# SingleSupplyAudioAmp.net
KiCad netlist of a schematic drawn in Altium Designer
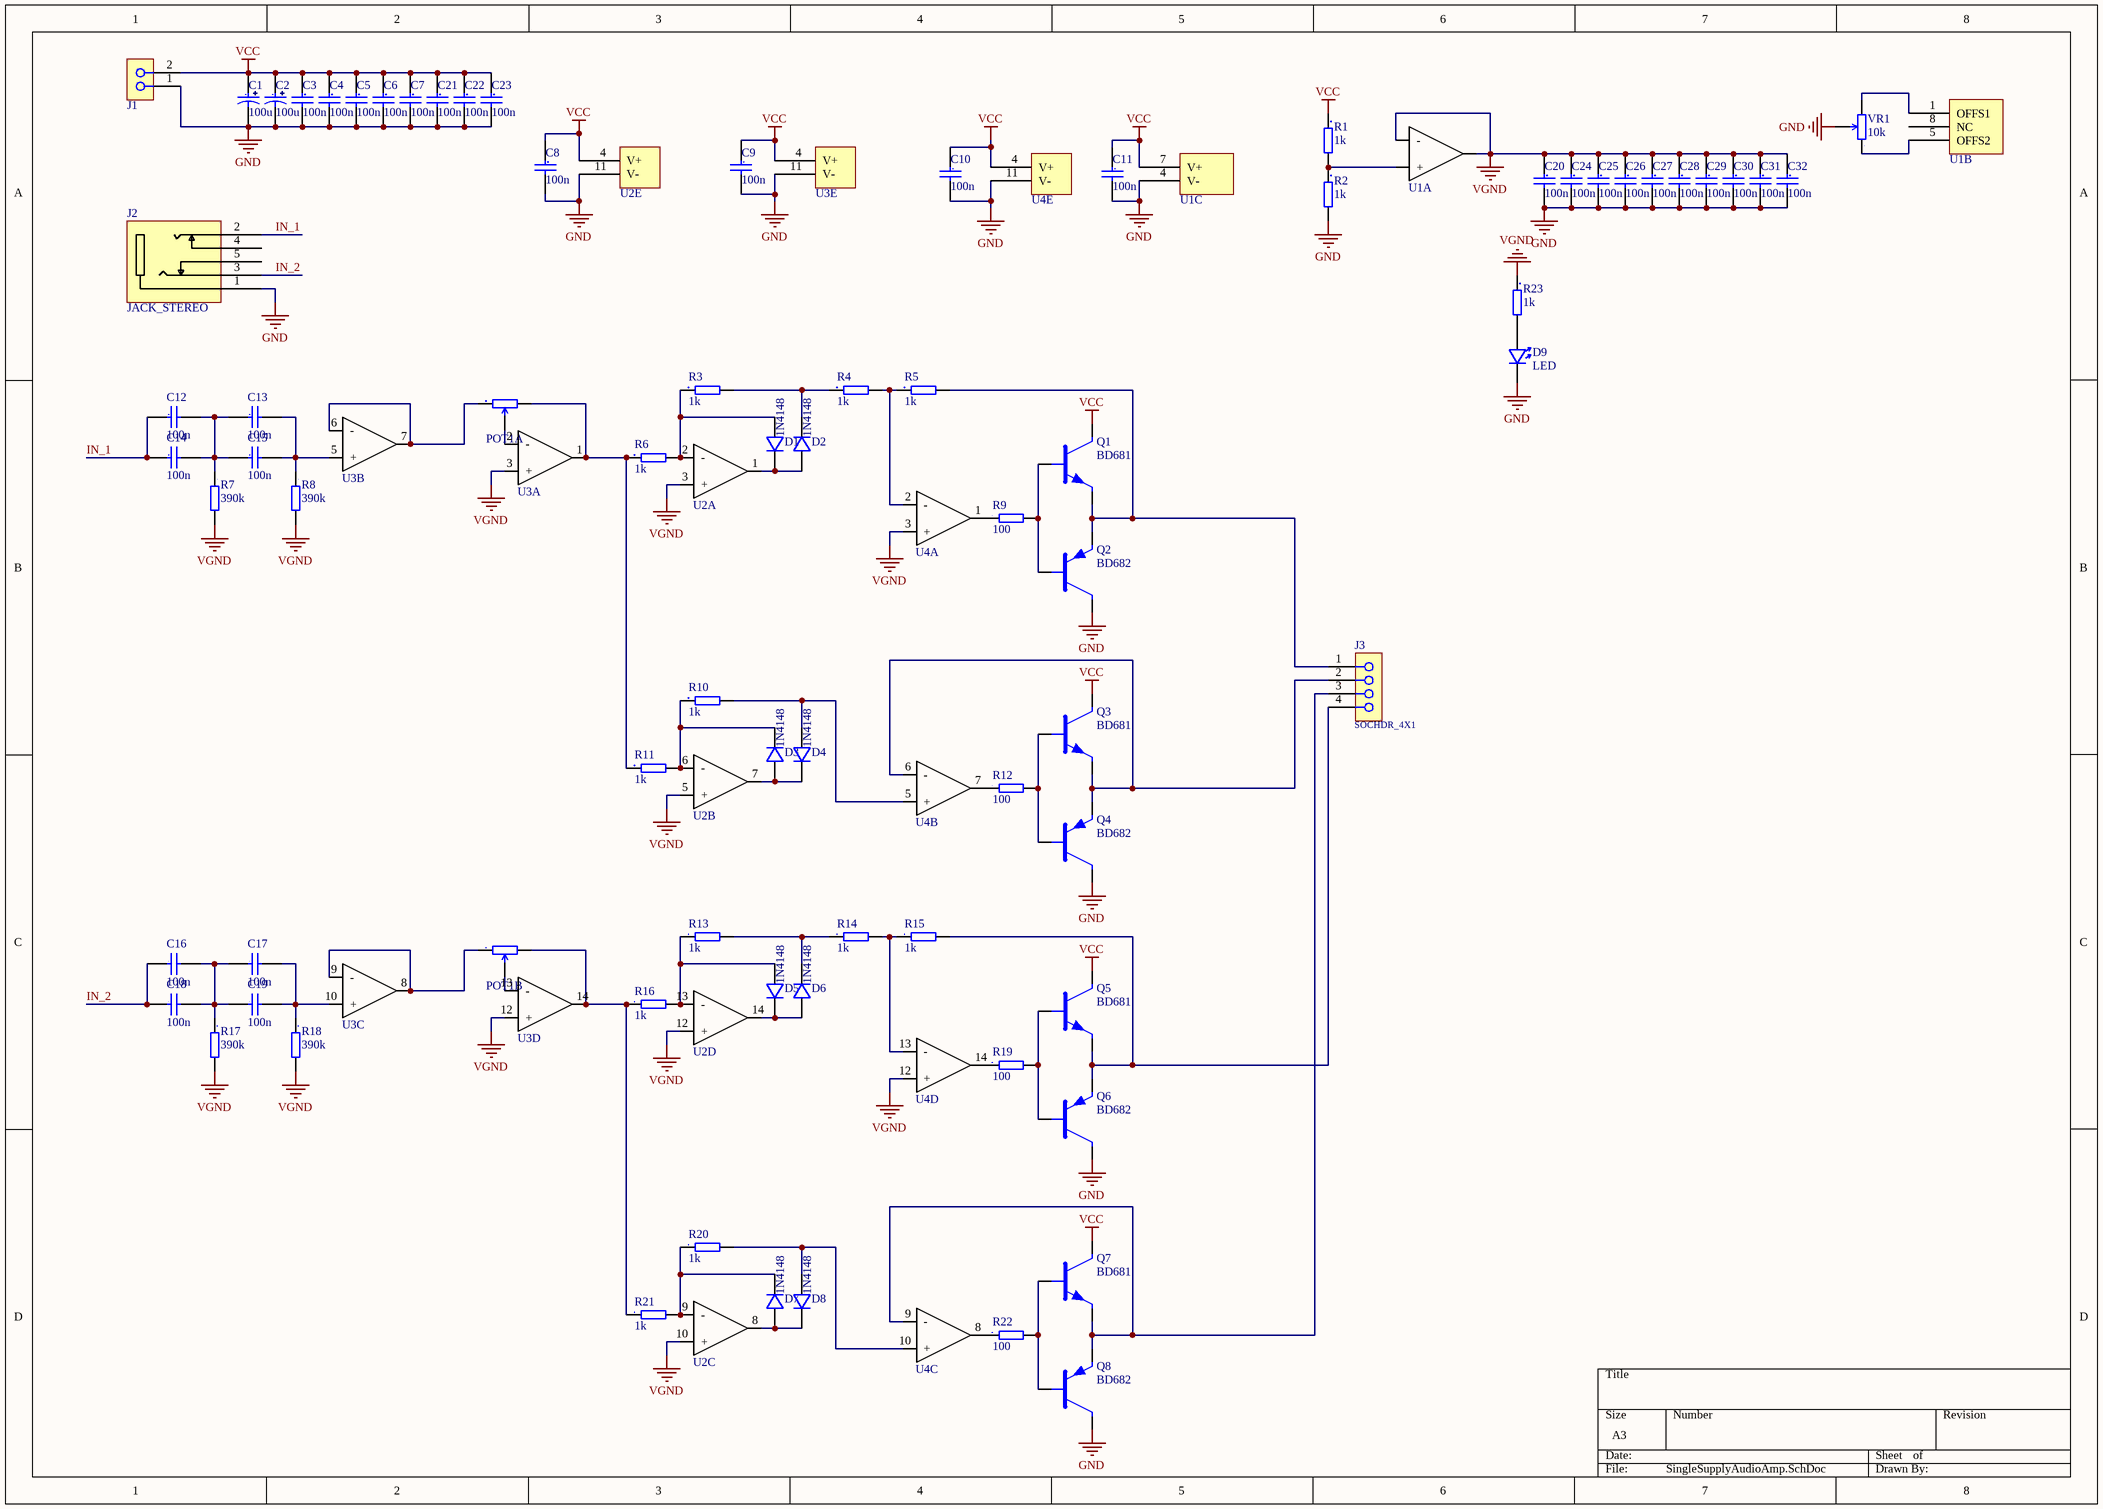
[diagram p0: SingleSupplyAudioAmp.SchDoc]

(export (version "E")
  (design (tool "Eeschema 10.0.6"))
  (components
    (comp (ref "C1") (value "100u") (footprint "C_TR3D") (libsource (lib "MyLib") (part "CAP_POL")))
    (comp (ref "C2") (value "100u") (footprint "C_TR3D") (libsource (lib "MyLib") (part "CAP_POL")))
    (comp (ref "C3") (value "100n") (footprint "C0603_N") (libsource (lib "MyLib") (part "CAP")))
    (comp (ref "C4") (value "100n") (footprint "C0603_N") (libsource (lib "MyLib") (part "CAP")))
    (comp (ref "C5") (value "100n") (footprint "C0603_N") (libsource (lib "MyLib") (part "CAP")))
    (comp (ref "C6") (value "100n") (footprint "C0603_N") (libsource (lib "MyLib") (part "CAP")))
    (comp (ref "C7") (value "100n") (footprint "C0603_N") (libsource (lib "MyLib") (part "CAP")))
    (comp (ref "C8") (value "100n") (footprint "C0603_N") (libsource (lib "MyLib") (part "CAP")))
    (comp (ref "C9") (value "100n") (footprint "C0603_N") (libsource (lib "MyLib") (part "CAP")))
    (comp (ref "C10") (value "100n") (footprint "C0603_N") (libsource (lib "MyLib") (part "CAP")))
    (comp (ref "C11") (value "100n") (footprint "C0603_N") (libsource (lib "MyLib") (part "CAP")))
    (comp (ref "C12") (value "100n") (footprint "C0603_N") (libsource (lib "MyLib") (part "CAP")))
    (comp (ref "C13") (value "100n") (footprint "C0603_N") (libsource (lib "MyLib") (part "CAP")))
    (comp (ref "C14") (value "100n") (footprint "C0603_N") (libsource (lib "MyLib") (part "CAP")))
    (comp (ref "C15") (value "100n") (footprint "C0603_N") (libsource (lib "MyLib") (part "CAP")))
    (comp (ref "C16") (value "100n") (footprint "C0603_N") (libsource (lib "MyLib") (part "CAP")))
    (comp (ref "C17") (value "100n") (footprint "C0603_N") (libsource (lib "MyLib") (part "CAP")))
    (comp (ref "C18") (value "100n") (footprint "C0603_N") (libsource (lib "MyLib") (part "CAP")))
    (comp (ref "C19") (value "100n") (footprint "C0603_N") (libsource (lib "MyLib") (part "CAP")))
    (comp (ref "C20") (value "100n") (footprint "C0603_N") (libsource (lib "MyLib") (part "CAP")))
    (comp (ref "C21") (value "100n") (footprint "C0603_N") (libsource (lib "MyLib") (part "CAP")))
    (comp (ref "C22") (value "100n") (footprint "C0603_N") (libsource (lib "MyLib") (part "CAP")))
    (comp (ref "C23") (value "100n") (footprint "C0603_N") (libsource (lib "MyLib") (part "CAP")))
    (comp (ref "C24") (value "100n") (footprint "C0603_N") (libsource (lib "MyLib") (part "CAP")))
    (comp (ref "C25") (value "100n") (footprint "C0603_N") (libsource (lib "MyLib") (part "CAP")))
    (comp (ref "C26") (value "100n") (footprint "C0603_N") (libsource (lib "MyLib") (part "CAP")))
    (comp (ref "C27") (value "100n") (footprint "C0603_N") (libsource (lib "MyLib") (part "CAP")))
    (comp (ref "C28") (value "100n") (footprint "C0603_N") (libsource (lib "MyLib") (part "CAP")))
    (comp (ref "C29") (value "100n") (footprint "C0603_N") (libsource (lib "MyLib") (part "CAP")))
    (comp (ref "C30") (value "100n") (footprint "C0603_N") (libsource (lib "MyLib") (part "CAP")))
    (comp (ref "C31") (value "100n") (footprint "C0603_N") (libsource (lib "MyLib") (part "CAP")))
    (comp (ref "C32") (value "100n") (footprint "C0603_N") (libsource (lib "MyLib") (part "CAP")))
    (comp (ref "D1") (value "1N4148") (footprint "DO-219AB") (libsource (lib "MyLib") (part "DIODE")))
    (comp (ref "D2") (value "1N4148") (footprint "DO-219AB") (libsource (lib "MyLib") (part "DIODE")))
    (comp (ref "D3") (value "1N4148") (footprint "DO-219AB") (libsource (lib "MyLib") (part "DIODE")))
    (comp (ref "D4") (value "1N4148") (footprint "DO-219AB") (libsource (lib "MyLib") (part "DIODE")))
    (comp (ref "D5") (value "1N4148") (footprint "DO-219AB") (libsource (lib "MyLib") (part "DIODE")))
    (comp (ref "D6") (value "1N4148") (footprint "DO-219AB") (libsource (lib "MyLib") (part "DIODE")))
    (comp (ref "D7") (value "1N4148") (footprint "DO-219AB") (libsource (lib "MyLib") (part "DIODE")))
    (comp (ref "D8") (value "1N4148") (footprint "DO-219AB") (libsource (lib "MyLib") (part "DIODE")))
    (comp (ref "D9") (value "LED") (footprint "LED_0603") (libsource (lib "MyLib") (part "LED")))
    (comp (ref "J1")
      (value "~")
      (footprint "TERM_BLOCK_2x1")
      (description "Socket")
      (libsource (lib "MyLib") (part "SOCHDR_2X1"))
    )
    (comp (ref "J2")
      (value "JACK_STEREO")
      (footprint "1503 09")
      (description "3,5mm Stereo Jack connector, Lumberg 1503 09 type")
      (libsource (lib "MyLib") (part "JACK_STEREO"))
    )
    (comp (ref "J3")
      (value "SOCHDR_4X1")
      (footprint "TERM_BLOCK_4x1")
      (description "Socket")
      (libsource (lib "MyLib") (part "SOCHDR_4X1"))
    )
    (comp (ref "POT1")
      (value "RES_POT_S")
      (footprint "POT_STEREO")
      (description "Stereo")
      (libsource (lib "") (part "RES_POT_S_1"))
    )
    (comp (ref "Q1") (value "BD681") (footprint "TO-126") (libsource (lib "MyLib") (part "BJT_NPN")))
    (comp (ref "Q2") (value "BD682") (footprint "TO-126") (libsource (lib "MyLib") (part "BJT_PNP")))
    (comp (ref "Q3") (value "BD681") (footprint "TO-126") (libsource (lib "MyLib") (part "BJT_NPN")))
    (comp (ref "Q4") (value "BD682") (footprint "TO-126") (libsource (lib "MyLib") (part "BJT_PNP")))
    (comp (ref "Q5") (value "BD681") (footprint "TO-126") (libsource (lib "MyLib") (part "BJT_NPN")))
    (comp (ref "Q6") (value "BD682") (footprint "TO-126") (libsource (lib "MyLib") (part "BJT_PNP")))
    (comp (ref "Q7") (value "BD681") (footprint "TO-126") (libsource (lib "MyLib") (part "BJT_NPN")))
    (comp (ref "Q8") (value "BD682") (footprint "TO-126") (libsource (lib "MyLib") (part "BJT_PNP")))
    (comp (ref "R1") (value "1k") (footprint "R0603_N") (libsource (lib "MyLib") (part "RES")))
    (comp (ref "R2") (value "1k") (footprint "R0603_N") (libsource (lib "MyLib") (part "RES")))
    (comp (ref "R3") (value "1k") (footprint "R0603_N") (libsource (lib "MyLib") (part "RES")))
    (comp (ref "R4") (value "1k") (footprint "R0603_N") (libsource (lib "MyLib") (part "RES")))
    (comp (ref "R5") (value "1k") (footprint "R0603_N") (libsource (lib "MyLib") (part "RES")))
    (comp (ref "R6") (value "1k") (footprint "R0603_N") (libsource (lib "MyLib") (part "RES")))
    (comp (ref "R7") (value "390k") (footprint "R0603_N") (libsource (lib "MyLib") (part "RES")))
    (comp (ref "R8") (value "390k") (footprint "R0603_N") (libsource (lib "MyLib") (part "RES")))
    (comp (ref "R9") (value "100") (footprint "R0603_N") (libsource (lib "MyLib") (part "RES")))
    (comp (ref "R10") (value "1k") (footprint "R0603_N") (libsource (lib "MyLib") (part "RES")))
    (comp (ref "R11") (value "1k") (footprint "R0603_N") (libsource (lib "MyLib") (part "RES")))
    (comp (ref "R12") (value "100") (footprint "R0603_N") (libsource (lib "MyLib") (part "RES")))
    (comp (ref "R13") (value "1k") (footprint "R0603_N") (libsource (lib "MyLib") (part "RES")))
    (comp (ref "R14") (value "1k") (footprint "R0603_N") (libsource (lib "MyLib") (part "RES")))
    (comp (ref "R15") (value "1k") (footprint "R0603_N") (libsource (lib "MyLib") (part "RES")))
    (comp (ref "R16") (value "1k") (footprint "R0603_N") (libsource (lib "MyLib") (part "RES")))
    (comp (ref "R17") (value "390k") (footprint "R0603_N") (libsource (lib "MyLib") (part "RES")))
    (comp (ref "R18") (value "390k") (footprint "R0603_N") (libsource (lib "MyLib") (part "RES")))
    (comp (ref "R19") (value "100") (footprint "R0603_N") (libsource (lib "MyLib") (part "RES")))
    (comp (ref "R20") (value "1k") (footprint "R0603_N") (libsource (lib "MyLib") (part "RES")))
    (comp (ref "R21") (value "1k") (footprint "R0603_N") (libsource (lib "MyLib") (part "RES")))
    (comp (ref "R22") (value "100") (footprint "R0603_N") (libsource (lib "MyLib") (part "RES")))
    (comp (ref "R23") (value "1k") (footprint "R0603_N") (libsource (lib "MyLib") (part "RES")))
    (comp (ref "U1")
      (value "uA741")
      (footprint "SOIC-8")
      (description "Rail-to-Rail, 90uV Vos, Precision op. amp.")
      (libsource (lib "MyLib") (part "uA741"))
    )
    (comp (ref "U2")
      (value "ADA4610-4")
      (footprint "SOIC-14")
      (description "Dual op. amp., Rail-to-Rail")
      (libsource (lib "MyLib") (part "ADA4610-4"))
    )
    (comp (ref "U3")
      (value "ADA4610-4")
      (footprint "SOIC-14")
      (description "Dual op. amp., Rail-to-Rail")
      (libsource (lib "MyLib") (part "ADA4610-4"))
    )
    (comp (ref "U4")
      (value "ADA4610-4")
      (footprint "SOIC-14")
      (description "Dual op. amp., Rail-to-Rail")
      (libsource (lib "MyLib") (part "ADA4610-4"))
    )
    (comp (ref "VR1")
      (value "10k")
      (footprint "POT_3364W")
      (description "Mono")
      (libsource (lib "MyLib") (part "RES_POT_M"))
    )
  )
  (nets
    (net (code "1") (name "/IN_1") (class "Default")
      (node (ref "C12") (pin "1") (pinfunction "1_1") (pintype "passive"))
      (node (ref "C14") (pin "1") (pinfunction "1_1") (pintype "passive"))
      (node (ref "J2") (pin "2") (pintype "passive"))
    )
    (net (code "2") (name "/IN_2") (class "Default")
      (node (ref "C16") (pin "1") (pinfunction "1_1") (pintype "passive"))
      (node (ref "C18") (pin "1") (pinfunction "1_1") (pintype "passive"))
      (node (ref "J2") (pin "3") (pintype "passive"))
    )
    (net (code "3") (name "GND") (class "Default")
      (node (ref "C1") (pin "N") (pinfunction "N_N") (pintype "passive"))
      (node (ref "C10") (pin "2") (pinfunction "2_2") (pintype "passive"))
      (node (ref "C11") (pin "2") (pinfunction "2_2") (pintype "passive"))
      (node (ref "C2") (pin "N") (pinfunction "N_N") (pintype "passive"))
      (node (ref "C20") (pin "2") (pinfunction "2_2") (pintype "passive"))
      (node (ref "C21") (pin "2") (pinfunction "2_2") (pintype "passive"))
      (node (ref "C22") (pin "2") (pinfunction "2_2") (pintype "passive"))
      (node (ref "C23") (pin "2") (pinfunction "2_2") (pintype "passive"))
      (node (ref "C24") (pin "2") (pinfunction "2_2") (pintype "passive"))
      (node (ref "C25") (pin "2") (pinfunction "2_2") (pintype "passive"))
      (node (ref "C26") (pin "2") (pinfunction "2_2") (pintype "passive"))
      (node (ref "C27") (pin "2") (pinfunction "2_2") (pintype "passive"))
      (node (ref "C28") (pin "2") (pinfunction "2_2") (pintype "passive"))
      (node (ref "C29") (pin "2") (pinfunction "2_2") (pintype "passive"))
      (node (ref "C3") (pin "2") (pinfunction "2_2") (pintype "passive"))
      (node (ref "C30") (pin "2") (pinfunction "2_2") (pintype "passive"))
      (node (ref "C31") (pin "2") (pinfunction "2_2") (pintype "passive"))
      (node (ref "C32") (pin "2") (pinfunction "2_2") (pintype "passive"))
      (node (ref "C4") (pin "2") (pinfunction "2_2") (pintype "passive"))
      (node (ref "C5") (pin "2") (pinfunction "2_2") (pintype "passive"))
      (node (ref "C6") (pin "2") (pinfunction "2_2") (pintype "passive"))
      (node (ref "C7") (pin "2") (pinfunction "2_2") (pintype "passive"))
      (node (ref "C8") (pin "2") (pinfunction "2_2") (pintype "passive"))
      (node (ref "C9") (pin "2") (pinfunction "2_2") (pintype "passive"))
      (node (ref "D9") (pin "K") (pinfunction "K_K") (pintype "passive"))
      (node (ref "J1") (pin "1") (pinfunction "1_1") (pintype "passive"))
      (node (ref "J2") (pin "1") (pintype "passive"))
      (node (ref "Q2") (pin "C") (pinfunction "C_C") (pintype "passive"))
      (node (ref "Q4") (pin "C") (pinfunction "C_C") (pintype "passive"))
      (node (ref "Q6") (pin "C") (pinfunction "C_C") (pintype "passive"))
      (node (ref "Q8") (pin "C") (pinfunction "C_C") (pintype "passive"))
      (node (ref "R2") (pin "2") (pinfunction "2_2") (pintype "passive"))
      (node (ref "U1") (pin "4") (pinfunction "V-_4") (pintype "passive"))
      (node (ref "U2") (pin "11") (pinfunction "V-_11") (pintype "passive"))
      (node (ref "U3") (pin "11") (pinfunction "V-_11") (pintype "passive"))
      (node (ref "U4") (pin "11") (pinfunction "V-_11") (pintype "passive"))
      (node (ref "VR1") (pin "WIPER") (pinfunction "WIPER_WIPER") (pintype "passive"))
    )
    (net (code "4") (name "Net-(C12-Pad2)") (class "Default")
      (node (ref "C12") (pin "2") (pinfunction "2_2") (pintype "passive"))
      (node (ref "C13") (pin "1") (pinfunction "1_1") (pintype "passive"))
      (node (ref "C14") (pin "2") (pinfunction "2_2") (pintype "passive"))
      (node (ref "C15") (pin "1") (pinfunction "1_1") (pintype "passive"))
      (node (ref "R7") (pin "1") (pinfunction "1_1") (pintype "passive"))
    )
    (net (code "5") (name "Net-(C16-Pad2)") (class "Default")
      (node (ref "C16") (pin "2") (pinfunction "2_2") (pintype "passive"))
      (node (ref "C17") (pin "1") (pinfunction "1_1") (pintype "passive"))
      (node (ref "C18") (pin "2") (pinfunction "2_2") (pintype "passive"))
      (node (ref "C19") (pin "1") (pinfunction "1_1") (pintype "passive"))
      (node (ref "R17") (pin "1") (pinfunction "1_1") (pintype "passive"))
    )
    (net (code "6") (name "Net-(D2-PadC)") (class "Default")
      (node (ref "D2") (pin "C") (pinfunction "C_C") (pintype "passive"))
      (node (ref "R3") (pin "2") (pinfunction "2_2") (pintype "passive"))
      (node (ref "R4") (pin "1") (pinfunction "1_1") (pintype "passive"))
    )
    (net (code "7") (name "Net-(D6-PadC)") (class "Default")
      (node (ref "D6") (pin "C") (pinfunction "C_C") (pintype "passive"))
      (node (ref "R13") (pin "2") (pinfunction "2_2") (pintype "passive"))
      (node (ref "R14") (pin "1") (pinfunction "1_1") (pintype "passive"))
    )
    (net (code "8") (name "Net-(D9-PadA)") (class "Default")
      (node (ref "D9") (pin "A") (pinfunction "A_A") (pintype "passive"))
      (node (ref "R23") (pin "2") (pinfunction "2_2") (pintype "passive"))
    )
    (net (code "9") (name "Net-(J3-Pad1)") (class "Default")
      (node (ref "J3") (pin "1") (pinfunction "1_1") (pintype "passive"))
      (node (ref "Q1") (pin "E") (pinfunction "E_E") (pintype "passive"))
      (node (ref "Q2") (pin "E") (pinfunction "E_E") (pintype "passive"))
      (node (ref "R5") (pin "2") (pinfunction "2_2") (pintype "passive"))
    )
    (net (code "10") (name "Net-(J3-Pad4)") (class "Default")
      (node (ref "J3") (pin "4") (pinfunction "4_4") (pintype "passive"))
      (node (ref "Q5") (pin "E") (pinfunction "E_E") (pintype "passive"))
      (node (ref "Q6") (pin "E") (pinfunction "E_E") (pintype "passive"))
      (node (ref "R15") (pin "2") (pinfunction "2_2") (pintype "passive"))
    )
    (net (code "11") (name "Net-(POT1A-CCW)") (class "Default")
      (node (ref "POT1") (pin "1") (pinfunction "CCW_1") (pintype "passive"))
      (node (ref "U3") (pin "6") (pinfunction "-_6") (pintype "passive"))
      (node (ref "U3") (pin "7") (pinfunction "Out_7") (pintype "passive"))
    )
    (net (code "12") (name "Net-(POT1A-CW)") (class "Default")
      (node (ref "POT1") (pin "3") (pinfunction "CW_3") (pintype "passive"))
      (node (ref "R11") (pin "1") (pinfunction "1_1") (pintype "passive"))
      (node (ref "R6") (pin "1") (pinfunction "1_1") (pintype "passive"))
      (node (ref "U3") (pin "1") (pinfunction "Out_1") (pintype "passive"))
    )
    (net (code "13") (name "Net-(POT1A-WIPER)") (class "Default")
      (node (ref "POT1") (pin "2") (pinfunction "WIPER_2") (pintype "passive"))
      (node (ref "U3") (pin "2") (pinfunction "-_2") (pintype "passive"))
    )
    (net (code "14") (name "Net-(POT1B-CCW)") (class "Default")
      (node (ref "POT1") (pin "4") (pinfunction "CCW_4") (pintype "passive"))
      (node (ref "U3") (pin "8") (pinfunction "Out_8") (pintype "passive"))
      (node (ref "U3") (pin "9") (pinfunction "-_9") (pintype "passive"))
    )
    (net (code "15") (name "Net-(POT1B-CW)") (class "Default")
      (node (ref "POT1") (pin "6") (pinfunction "CW_6") (pintype "passive"))
      (node (ref "R16") (pin "1") (pinfunction "1_1") (pintype "passive"))
      (node (ref "R21") (pin "1") (pinfunction "1_1") (pintype "passive"))
      (node (ref "U3") (pin "14") (pinfunction "Out_14") (pintype "passive"))
    )
    (net (code "16") (name "Net-(POT1B-WIPER)") (class "Default")
      (node (ref "POT1") (pin "5") (pinfunction "WIPER_5") (pintype "passive"))
      (node (ref "U3") (pin "13") (pinfunction "-_13") (pintype "passive"))
    )
    (net (code "17") (name "Net-(Q1-PadB)") (class "Default")
      (node (ref "Q1") (pin "B") (pinfunction "B_B") (pintype "passive"))
      (node (ref "Q2") (pin "B") (pinfunction "B_B") (pintype "passive"))
      (node (ref "R9") (pin "2") (pinfunction "2_2") (pintype "passive"))
    )
    (net (code "18") (name "Net-(Q3-PadB)") (class "Default")
      (node (ref "Q3") (pin "B") (pinfunction "B_B") (pintype "passive"))
      (node (ref "Q4") (pin "B") (pinfunction "B_B") (pintype "passive"))
      (node (ref "R12") (pin "2") (pinfunction "2_2") (pintype "passive"))
    )
    (net (code "19") (name "Net-(Q5-PadB)") (class "Default")
      (node (ref "Q5") (pin "B") (pinfunction "B_B") (pintype "passive"))
      (node (ref "Q6") (pin "B") (pinfunction "B_B") (pintype "passive"))
      (node (ref "R19") (pin "2") (pinfunction "2_2") (pintype "passive"))
    )
    (net (code "20") (name "Net-(Q7-PadB)") (class "Default")
      (node (ref "Q7") (pin "B") (pinfunction "B_B") (pintype "passive"))
      (node (ref "Q8") (pin "B") (pinfunction "B_B") (pintype "passive"))
      (node (ref "R22") (pin "2") (pinfunction "2_2") (pintype "passive"))
    )
    (net (code "21") (name "Net-(U1A-+)") (class "Default")
      (node (ref "R1") (pin "2") (pinfunction "2_2") (pintype "passive"))
      (node (ref "R2") (pin "1") (pinfunction "1_1") (pintype "passive"))
      (node (ref "U1") (pin "3") (pinfunction "+_3") (pintype "passive"))
    )
    (net (code "22") (name "Net-(U1B-OFFS1)") (class "Default")
      (node (ref "U1") (pin "1") (pinfunction "OFFS1_1") (pintype "passive"))
      (node (ref "VR1") (pin "CW") (pinfunction "CW_CW") (pintype "passive"))
    )
    (net (code "23") (name "Net-(U1B-OFFS2)") (class "Default")
      (node (ref "U1") (pin "5") (pinfunction "OFFS2_5") (pintype "passive"))
      (node (ref "VR1") (pin "CCW") (pinfunction "CCW_CCW") (pintype "passive"))
    )
    (net (code "24") (name "Net-(U2A--)") (class "Default")
      (node (ref "D1") (pin "A") (pinfunction "A_A") (pintype "passive"))
      (node (ref "R3") (pin "1") (pinfunction "1_1") (pintype "passive"))
      (node (ref "R6") (pin "2") (pinfunction "2_2") (pintype "passive"))
      (node (ref "U2") (pin "2") (pinfunction "-_2") (pintype "passive"))
    )
    (net (code "25") (name "Net-(U2A-Out)") (class "Default")
      (node (ref "D1") (pin "C") (pinfunction "C_C") (pintype "passive"))
      (node (ref "D2") (pin "A") (pinfunction "A_A") (pintype "passive"))
      (node (ref "U2") (pin "1") (pinfunction "Out_1") (pintype "passive"))
    )
    (net (code "26") (name "Net-(U2B--)") (class "Default")
      (node (ref "D3") (pin "C") (pinfunction "C_C") (pintype "passive"))
      (node (ref "R10") (pin "1") (pinfunction "1_1") (pintype "passive"))
      (node (ref "R11") (pin "2") (pinfunction "2_2") (pintype "passive"))
      (node (ref "U2") (pin "6") (pinfunction "-_6") (pintype "passive"))
    )
    (net (code "27") (name "Net-(U2B-Out)") (class "Default")
      (node (ref "D3") (pin "A") (pinfunction "A_A") (pintype "passive"))
      (node (ref "D4") (pin "C") (pinfunction "C_C") (pintype "passive"))
      (node (ref "U2") (pin "7") (pinfunction "Out_7") (pintype "passive"))
    )
    (net (code "28") (name "Net-(U2C--)") (class "Default")
      (node (ref "D7") (pin "C") (pinfunction "C_C") (pintype "passive"))
      (node (ref "R20") (pin "1") (pinfunction "1_1") (pintype "passive"))
      (node (ref "R21") (pin "2") (pinfunction "2_2") (pintype "passive"))
      (node (ref "U2") (pin "9") (pinfunction "-_9") (pintype "passive"))
    )
    (net (code "29") (name "Net-(U2C-Out)") (class "Default")
      (node (ref "D7") (pin "A") (pinfunction "A_A") (pintype "passive"))
      (node (ref "D8") (pin "C") (pinfunction "C_C") (pintype "passive"))
      (node (ref "U2") (pin "8") (pinfunction "Out_8") (pintype "passive"))
    )
    (net (code "30") (name "Net-(U2D--)") (class "Default")
      (node (ref "D5") (pin "A") (pinfunction "A_A") (pintype "passive"))
      (node (ref "R13") (pin "1") (pinfunction "1_1") (pintype "passive"))
      (node (ref "R16") (pin "2") (pinfunction "2_2") (pintype "passive"))
      (node (ref "U2") (pin "13") (pinfunction "-_13") (pintype "passive"))
    )
    (net (code "31") (name "Net-(U2D-Out)") (class "Default")
      (node (ref "D5") (pin "C") (pinfunction "C_C") (pintype "passive"))
      (node (ref "D6") (pin "A") (pinfunction "A_A") (pintype "passive"))
      (node (ref "U2") (pin "14") (pinfunction "Out_14") (pintype "passive"))
    )
    (net (code "32") (name "Net-(U3B-+)") (class "Default")
      (node (ref "C13") (pin "2") (pinfunction "2_2") (pintype "passive"))
      (node (ref "C15") (pin "2") (pinfunction "2_2") (pintype "passive"))
      (node (ref "R8") (pin "1") (pinfunction "1_1") (pintype "passive"))
      (node (ref "U3") (pin "5") (pinfunction "+_5") (pintype "passive"))
    )
    (net (code "33") (name "Net-(U3C-+)") (class "Default")
      (node (ref "C17") (pin "2") (pinfunction "2_2") (pintype "passive"))
      (node (ref "C19") (pin "2") (pinfunction "2_2") (pintype "passive"))
      (node (ref "R18") (pin "1") (pinfunction "1_1") (pintype "passive"))
      (node (ref "U3") (pin "10") (pinfunction "+_10") (pintype "passive"))
    )
    (net (code "34") (name "Net-(U4A--)") (class "Default")
      (node (ref "R4") (pin "2") (pinfunction "2_2") (pintype "passive"))
      (node (ref "R5") (pin "1") (pinfunction "1_1") (pintype "passive"))
      (node (ref "U4") (pin "2") (pinfunction "-_2") (pintype "passive"))
    )
    (net (code "35") (name "Net-(U4A-Out)") (class "Default")
      (node (ref "R9") (pin "1") (pinfunction "1_1") (pintype "passive"))
      (node (ref "U4") (pin "1") (pinfunction "Out_1") (pintype "passive"))
    )
    (net (code "36") (name "Net-(U4B-+)") (class "Default")
      (node (ref "D4") (pin "A") (pinfunction "A_A") (pintype "passive"))
      (node (ref "R10") (pin "2") (pinfunction "2_2") (pintype "passive"))
      (node (ref "U4") (pin "5") (pinfunction "+_5") (pintype "passive"))
    )
    (net (code "37") (name "Net-(U4B--)") (class "Default")
      (node (ref "J3") (pin "2") (pinfunction "2_2") (pintype "passive"))
      (node (ref "Q3") (pin "E") (pinfunction "E_E") (pintype "passive"))
      (node (ref "Q4") (pin "E") (pinfunction "E_E") (pintype "passive"))
      (node (ref "U4") (pin "6") (pinfunction "-_6") (pintype "passive"))
    )
    (net (code "38") (name "Net-(U4B-Out)") (class "Default")
      (node (ref "R12") (pin "1") (pinfunction "1_1") (pintype "passive"))
      (node (ref "U4") (pin "7") (pinfunction "Out_7") (pintype "passive"))
    )
    (net (code "39") (name "Net-(U4C-+)") (class "Default")
      (node (ref "D8") (pin "A") (pinfunction "A_A") (pintype "passive"))
      (node (ref "R20") (pin "2") (pinfunction "2_2") (pintype "passive"))
      (node (ref "U4") (pin "10") (pinfunction "+_10") (pintype "passive"))
    )
    (net (code "40") (name "Net-(U4C--)") (class "Default")
      (node (ref "J3") (pin "3") (pinfunction "3_3") (pintype "passive"))
      (node (ref "Q7") (pin "E") (pinfunction "E_E") (pintype "passive"))
      (node (ref "Q8") (pin "E") (pinfunction "E_E") (pintype "passive"))
      (node (ref "U4") (pin "9") (pinfunction "-_9") (pintype "passive"))
    )
    (net (code "41") (name "Net-(U4C-Out)") (class "Default")
      (node (ref "R22") (pin "1") (pinfunction "1_1") (pintype "passive"))
      (node (ref "U4") (pin "8") (pinfunction "Out_8") (pintype "passive"))
    )
    (net (code "42") (name "Net-(U4D--)") (class "Default")
      (node (ref "R14") (pin "2") (pinfunction "2_2") (pintype "passive"))
      (node (ref "R15") (pin "1") (pinfunction "1_1") (pintype "passive"))
      (node (ref "U4") (pin "13") (pinfunction "-_13") (pintype "passive"))
    )
    (net (code "43") (name "Net-(U4D-Out)") (class "Default")
      (node (ref "R19") (pin "1") (pinfunction "1_1") (pintype "passive"))
      (node (ref "U4") (pin "14") (pinfunction "Out_14") (pintype "passive"))
    )
    (net (code "44") (name "VCC") (class "Default")
      (node (ref "C1") (pin "P") (pinfunction "P_P") (pintype "passive"))
      (node (ref "C10") (pin "1") (pinfunction "1_1") (pintype "passive"))
      (node (ref "C11") (pin "1") (pinfunction "1_1") (pintype "passive"))
      (node (ref "C2") (pin "P") (pinfunction "P_P") (pintype "passive"))
      (node (ref "C21") (pin "1") (pinfunction "1_1") (pintype "passive"))
      (node (ref "C22") (pin "1") (pinfunction "1_1") (pintype "passive"))
      (node (ref "C23") (pin "1") (pinfunction "1_1") (pintype "passive"))
      (node (ref "C3") (pin "1") (pinfunction "1_1") (pintype "passive"))
      (node (ref "C4") (pin "1") (pinfunction "1_1") (pintype "passive"))
      (node (ref "C5") (pin "1") (pinfunction "1_1") (pintype "passive"))
      (node (ref "C6") (pin "1") (pinfunction "1_1") (pintype "passive"))
      (node (ref "C7") (pin "1") (pinfunction "1_1") (pintype "passive"))
      (node (ref "C8") (pin "1") (pinfunction "1_1") (pintype "passive"))
      (node (ref "C9") (pin "1") (pinfunction "1_1") (pintype "passive"))
      (node (ref "J1") (pin "2") (pinfunction "2_2") (pintype "passive"))
      (node (ref "Q1") (pin "C") (pinfunction "C_C") (pintype "passive"))
      (node (ref "Q3") (pin "C") (pinfunction "C_C") (pintype "passive"))
      (node (ref "Q5") (pin "C") (pinfunction "C_C") (pintype "passive"))
      (node (ref "Q7") (pin "C") (pinfunction "C_C") (pintype "passive"))
      (node (ref "R1") (pin "1") (pinfunction "1_1") (pintype "passive"))
      (node (ref "U1") (pin "7") (pinfunction "V+_7") (pintype "passive"))
      (node (ref "U2") (pin "4") (pinfunction "V+_4") (pintype "passive"))
      (node (ref "U3") (pin "4") (pinfunction "V+_4") (pintype "passive"))
      (node (ref "U4") (pin "4") (pinfunction "V+_4") (pintype "passive"))
    )
    (net (code "45") (name "VGND") (class "Default")
      (node (ref "C20") (pin "1") (pinfunction "1_1") (pintype "passive"))
      (node (ref "C24") (pin "1") (pinfunction "1_1") (pintype "passive"))
      (node (ref "C25") (pin "1") (pinfunction "1_1") (pintype "passive"))
      (node (ref "C26") (pin "1") (pinfunction "1_1") (pintype "passive"))
      (node (ref "C27") (pin "1") (pinfunction "1_1") (pintype "passive"))
      (node (ref "C28") (pin "1") (pinfunction "1_1") (pintype "passive"))
      (node (ref "C29") (pin "1") (pinfunction "1_1") (pintype "passive"))
      (node (ref "C30") (pin "1") (pinfunction "1_1") (pintype "passive"))
      (node (ref "C31") (pin "1") (pinfunction "1_1") (pintype "passive"))
      (node (ref "C32") (pin "1") (pinfunction "1_1") (pintype "passive"))
      (node (ref "R17") (pin "2") (pinfunction "2_2") (pintype "passive"))
      (node (ref "R18") (pin "2") (pinfunction "2_2") (pintype "passive"))
      (node (ref "R23") (pin "1") (pinfunction "1_1") (pintype "passive"))
      (node (ref "R7") (pin "2") (pinfunction "2_2") (pintype "passive"))
      (node (ref "R8") (pin "2") (pinfunction "2_2") (pintype "passive"))
      (node (ref "U1") (pin "2") (pinfunction "-_2") (pintype "passive"))
      (node (ref "U1") (pin "6") (pinfunction "Out_6") (pintype "passive"))
      (node (ref "U2") (pin "10") (pinfunction "+_10") (pintype "passive"))
      (node (ref "U2") (pin "12") (pinfunction "+_12") (pintype "passive"))
      (node (ref "U2") (pin "3") (pinfunction "+_3") (pintype "passive"))
      (node (ref "U2") (pin "5") (pinfunction "+_5") (pintype "passive"))
      (node (ref "U3") (pin "12") (pinfunction "+_12") (pintype "passive"))
      (node (ref "U3") (pin "3") (pinfunction "+_3") (pintype "passive"))
      (node (ref "U4") (pin "12") (pinfunction "+_12") (pintype "passive"))
      (node (ref "U4") (pin "3") (pinfunction "+_3") (pintype "passive"))
    )
    (net (code "46") (name "unconnected-(J2-Pad4)") (class "Default")
      (node (ref "J2") (pin "4") (pintype "passive"))
    )
    (net (code "47") (name "unconnected-(J2-Pad5)") (class "Default")
      (node (ref "J2") (pin "5") (pintype "passive"))
    )
    (net (code "48") (name "unconnected-(U1B-NC-Pad8)") (class "Default")
      (node (ref "U1") (pin "8") (pinfunction "NC_8") (pintype "passive"))
    )
  )
)
